# 05-mcu3.net
KiCad netlist of a schematic drawn in Altium Designer
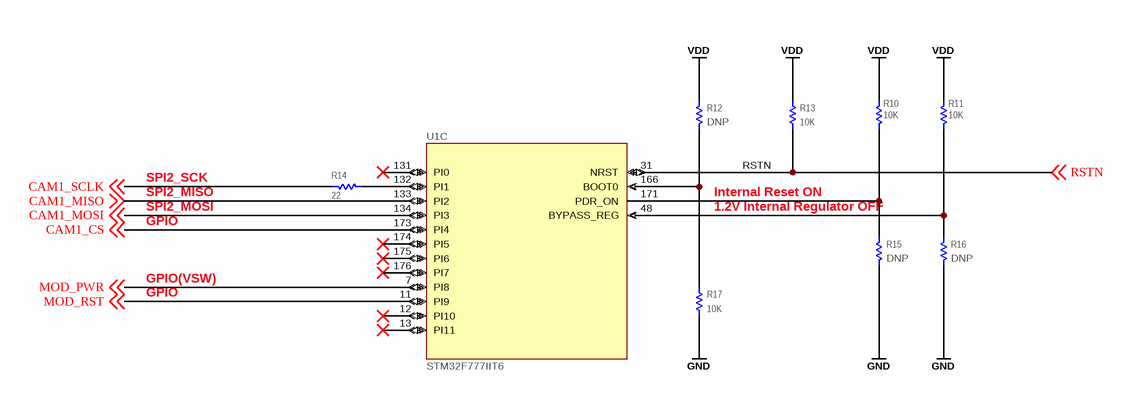
[diagram p0: 05-mcu3.SchDoc]

(export (version "E")
  (design (tool "Eeschema 10.0.6"))
  (components
    (comp (ref "R10")
      (value "10K")
      (footprint "RESC2012X70N")
      (description "Thick Film Resistor 10k ±1% 0805")
      (fields (field (name "MANUFACTURER") "Panasonic") (field (name "TOLERANCE") "±1%"))
      (libsource (lib "Graviton") (part "RES 0402"))
    )
    (comp (ref "R11")
      (value "10K")
      (footprint "RESC2012X70N")
      (description "Thick Film Resistor 10k ±1% 0805")
      (fields (field (name "MANUFACTURER") "Panasonic") (field (name "TOLERANCE") "±1%"))
      (libsource (lib "Graviton") (part "RES 0402"))
    )
    (comp (ref "R12")
      (value "ERJ-6ENF1002V")
      (footprint "RESC2012X70N")
      (description "Thick Film Resistor 10k ±1% 0805")
      (fields
        (field (name "MANUFACTURER") "Panasonic")
        (field (name "TOLERANCE") "±1%")
        (field (name "DO NOT PLACE") "DNP")
      )
      (libsource (lib "Graviton") (part "RES 0402"))
    )
    (comp (ref "R13")
      (value "10K")
      (footprint "RESC2012X70N")
      (description "Thick Film Resistor 10k ±1% 0805")
      (fields (field (name "MANUFACTURER") "Panasonic") (field (name "TOLERANCE") "±1%"))
      (libsource (lib "Graviton") (part "RES 0402"))
    )
    (comp (ref "R14")
      (value "22")
      (footprint "RESC2012X70N")
      (description "Thick Film Resistor 22 ±1% 0805")
      (fields (field (name "MANUFACTURER") "Panasonic") (field (name "TOLERANCE") "±1%"))
      (libsource (lib "Graviton") (part "RES 0402"))
    )
    (comp (ref "R15")
      (value "ERJ-6ENF1002V")
      (footprint "RESC2012X70N")
      (description "Thick Film Resistor 10k ±1% 0805")
      (fields
        (field (name "MANUFACTURER") "Panasonic")
        (field (name "TOLERANCE") "±1%")
        (field (name "DO NOT PLACE") "DNP")
      )
      (libsource (lib "Graviton") (part "RES 0402"))
    )
    (comp (ref "R16")
      (value "ERJ-6ENF1002V")
      (footprint "RESC2012X70N")
      (description "Thick Film Resistor 10k ±1% 0805")
      (fields
        (field (name "MANUFACTURER") "Panasonic")
        (field (name "TOLERANCE") "±1%")
        (field (name "DO NOT PLACE") "DNP")
      )
      (libsource (lib "Graviton") (part "RES 0402"))
    )
    (comp (ref "R17")
      (value "10K")
      (footprint "RESC2012X70N")
      (description "Thick Film Resistor 10k ±1% 0805")
      (fields (field (name "MANUFACTURER") "Panasonic") (field (name "TOLERANCE") "±1%"))
      (libsource (lib "Graviton") (part "RES 0402"))
    )
    (comp (ref "U1")
      (value "STM32F777IIT6")
      (footprint "st:TSQFP50P2600X2600X160-176N")
      (description "Microcontroller")
      (fields (field (name "MANUFACTURER") "STMicroelectronics"))
      (libsource (lib "st") (part "STM32F777IIT"))
    )
  )
  (nets
    (net (code "1") (name "CAM1_CS") (class "Default")
      (node (ref "U1") (pin "173") (pinfunction "PI4_173") (pintype "bidirectional"))
    )
    (net (code "2") (name "CAM1_MISO") (class "Default")
      (node (ref "U1") (pin "133") (pinfunction "PI2_133") (pintype "bidirectional"))
    )
    (net (code "3") (name "CAM1_MOSI") (class "Default")
      (node (ref "U1") (pin "134") (pinfunction "PI3_134") (pintype "bidirectional"))
    )
    (net (code "4") (name "CAM1_SCLK") (class "Default")
      (node (ref "R14") (pin "1") (pinfunction "1_1") (pintype "passive"))
    )
    (net (code "5") (name "GND") (class "Default")
      (node (ref "R15") (pin "1") (pinfunction "1_1") (pintype "passive"))
      (node (ref "R16") (pin "1") (pinfunction "1_1") (pintype "passive"))
      (node (ref "R17") (pin "1") (pinfunction "1_1") (pintype "passive"))
    )
    (net (code "6") (name "MOD_PWR") (class "Default")
      (node (ref "U1") (pin "7") (pinfunction "PI8_7") (pintype "bidirectional"))
    )
    (net (code "7") (name "MOD_RST") (class "Default")
      (node (ref "U1") (pin "11") (pinfunction "PI9_11") (pintype "bidirectional"))
    )
    (net (code "8") (name "Net-(U1C-BOOT0)") (class "Default")
      (node (ref "R12") (pin "1") (pinfunction "1_1") (pintype "passive"))
      (node (ref "R17") (pin "2") (pinfunction "2_2") (pintype "passive"))
      (node (ref "U1") (pin "166") (pinfunction "BOOT0_166") (pintype "input"))
    )
    (net (code "9") (name "Net-(U1C-BYPASS_REG)") (class "Default")
      (node (ref "R11") (pin "1") (pinfunction "1_1") (pintype "passive"))
      (node (ref "R16") (pin "2") (pinfunction "2_2") (pintype "passive"))
      (node (ref "U1") (pin "48") (pinfunction "BYPASS_REG_48") (pintype "input"))
    )
    (net (code "10") (name "Net-(U1C-PDR_ON)") (class "Default")
      (node (ref "R10") (pin "1") (pinfunction "1_1") (pintype "passive"))
      (node (ref "R15") (pin "2") (pinfunction "2_2") (pintype "passive"))
      (node (ref "U1") (pin "171") (pinfunction "PDR_ON_171") (pintype "passive"))
    )
    (net (code "11") (name "Net-(U1C-PI1)") (class "Default")
      (node (ref "R14") (pin "2") (pinfunction "2_2") (pintype "passive"))
      (node (ref "U1") (pin "132") (pinfunction "PI1_132") (pintype "bidirectional"))
    )
    (net (code "12") (name "RSTN") (class "Default")
      (node (ref "R13") (pin "1") (pinfunction "1_1") (pintype "passive"))
      (node (ref "U1") (pin "31") (pinfunction "NRST_31") (pintype "bidirectional"))
    )
    (net (code "13") (name "VDD") (class "Default")
      (node (ref "R10") (pin "2") (pinfunction "2_2") (pintype "passive"))
      (node (ref "R11") (pin "2") (pinfunction "2_2") (pintype "passive"))
      (node (ref "R12") (pin "2") (pinfunction "2_2") (pintype "passive"))
      (node (ref "R13") (pin "2") (pinfunction "2_2") (pintype "passive"))
    )
    (net (code "14") (name "unconnected-(U1C-PI0-Pad131)") (class "Default")
      (node (ref "U1") (pin "131") (pinfunction "PI0_131") (pintype "bidirectional+no_connect"))
    )
    (net (code "15") (name "unconnected-(U1C-PI5-Pad174)") (class "Default")
      (node (ref "U1") (pin "174") (pinfunction "PI5_174") (pintype "bidirectional+no_connect"))
    )
    (net (code "16") (name "unconnected-(U1C-PI6-Pad175)") (class "Default")
      (node (ref "U1") (pin "175") (pinfunction "PI6_175") (pintype "bidirectional+no_connect"))
    )
    (net (code "17") (name "unconnected-(U1C-PI7-Pad176)") (class "Default")
      (node (ref "U1") (pin "176") (pinfunction "PI7_176") (pintype "bidirectional+no_connect"))
    )
    (net (code "18") (name "unconnected-(U1C-PI10-Pad12)") (class "Default")
      (node (ref "U1") (pin "12") (pinfunction "PI10_12") (pintype "bidirectional+no_connect"))
    )
    (net (code "19") (name "unconnected-(U1C-PI11-Pad13)") (class "Default")
      (node (ref "U1") (pin "13") (pinfunction "PI11_13") (pintype "bidirectional+no_connect"))
    )
  )
)
